# link_logic.net
KiCad netlist of a schematic drawn in Altium Designer
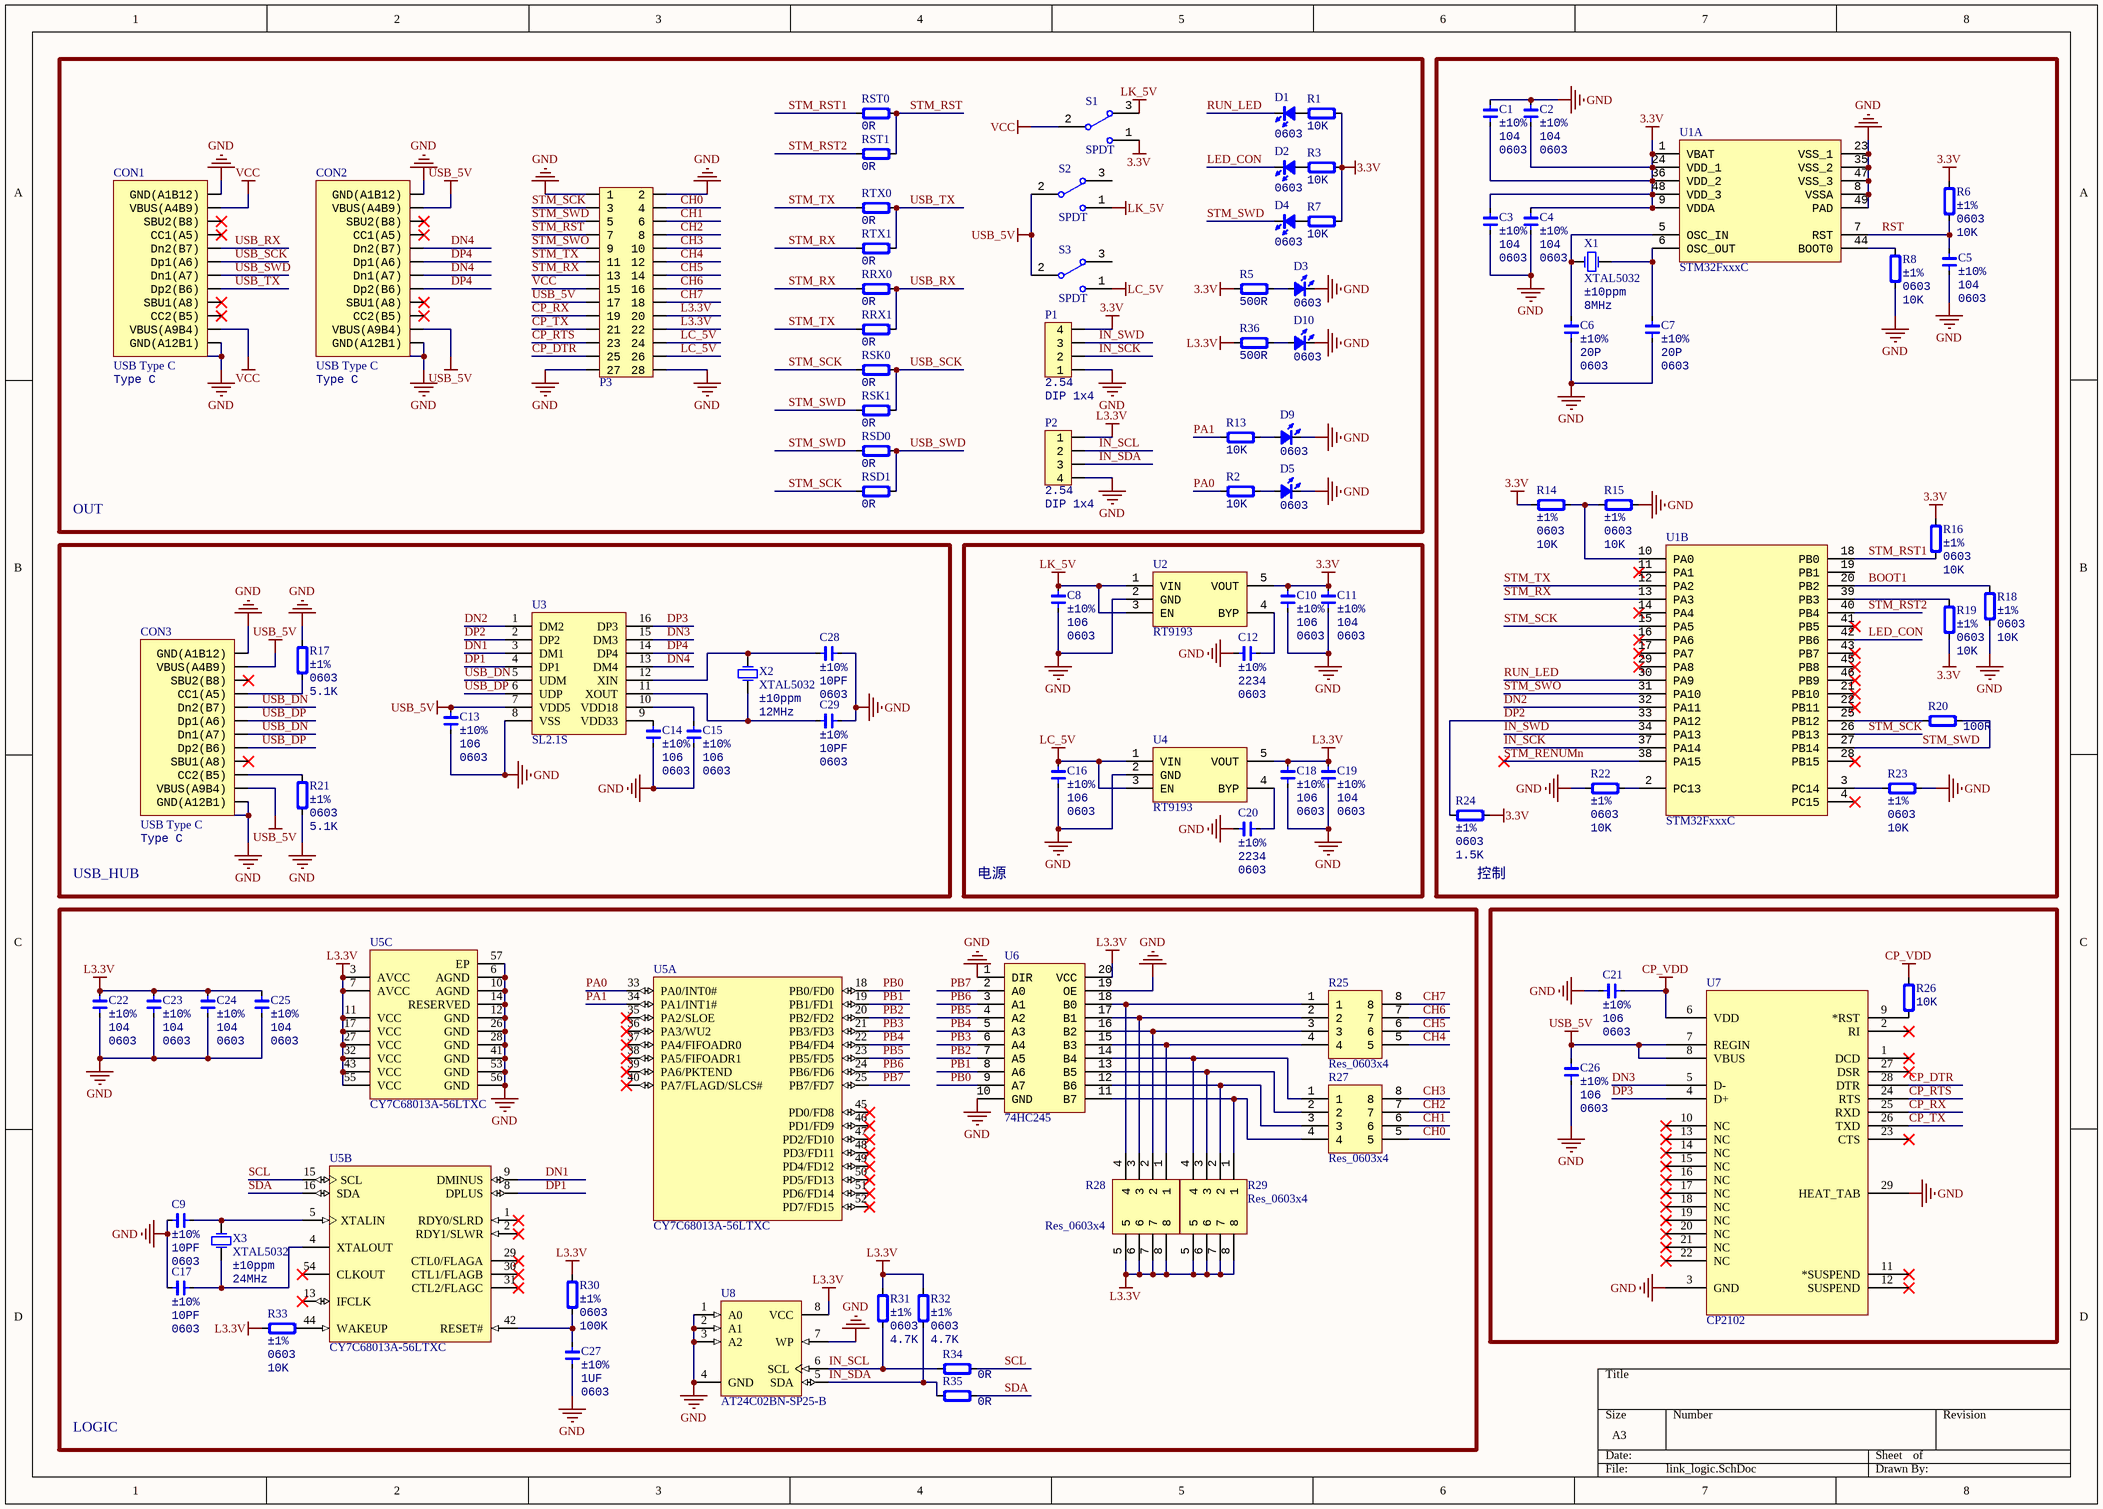
[diagram p0: link_logic.SchDoc]

(export (version "E")
  (design (tool "Eeschema 10.0.6"))
  (components
    (comp (ref "C1")
      (value "104")
      (footprint "CAP_0603")
      (description "Capacitor")
      (fields (field (name "NOTE") "±10%") (field (name "TYPE") "0603") (field (name "Comment") "C0603"))
      (libsource (lib "Integrated_Library") (part "Cap_0603"))
    )
    (comp (ref "C2")
      (value "104")
      (footprint "CAP_0603")
      (description "Capacitor")
      (fields (field (name "NOTE") "±10%") (field (name "TYPE") "0603") (field (name "Comment") "C0603"))
      (libsource (lib "Integrated_Library") (part "Cap_0603"))
    )
    (comp (ref "C3")
      (value "104")
      (footprint "CAP_0603")
      (description "Capacitor")
      (fields (field (name "NOTE") "±10%") (field (name "TYPE") "0603") (field (name "Comment") "C0603"))
      (libsource (lib "Integrated_Library") (part "Cap_0603"))
    )
    (comp (ref "C4")
      (value "104")
      (footprint "CAP_0603")
      (description "Capacitor")
      (fields (field (name "NOTE") "±10%") (field (name "TYPE") "0603") (field (name "Comment") "C0603"))
      (libsource (lib "Integrated_Library") (part "Cap_0603"))
    )
    (comp (ref "C5")
      (value "104")
      (footprint "CAP_0603")
      (description "Capacitor")
      (fields (field (name "NOTE") "±10%") (field (name "TYPE") "0603") (field (name "Comment") "C0603"))
      (libsource (lib "Integrated_Library") (part "Cap_0603"))
    )
    (comp (ref "C6")
      (value "20P")
      (footprint "CAP_0603")
      (description "Capacitor")
      (fields (field (name "NOTE") "±10%") (field (name "TYPE") "0603") (field (name "Comment") "C0603"))
      (libsource (lib "Integrated_Library") (part "Cap_0603"))
    )
    (comp (ref "C7")
      (value "20P")
      (footprint "CAP_0603")
      (description "Capacitor")
      (fields (field (name "NOTE") "±10%") (field (name "TYPE") "0603") (field (name "Comment") "C0603"))
      (libsource (lib "Integrated_Library") (part "Cap_0603"))
    )
    (comp (ref "C8")
      (value "106")
      (footprint "CAP_0603")
      (description "Capacitor")
      (fields (field (name "NOTE") "±10%") (field (name "TYPE") "0603") (field (name "Comment") "C0603"))
      (libsource (lib "Integrated_Library") (part "Cap_0603"))
    )
    (comp (ref "C9")
      (value "10PF")
      (footprint "CAP_0603")
      (description "Capacitor")
      (fields (field (name "NOTE") "±10%") (field (name "TYPE") "0603") (field (name "Comment") "C0603"))
      (libsource (lib "") (part "Cap_0603_3"))
    )
    (comp (ref "C10")
      (value "106")
      (footprint "CAP_0603")
      (description "Capacitor")
      (fields (field (name "NOTE") "±10%") (field (name "TYPE") "0603") (field (name "Comment") "C0603"))
      (libsource (lib "Integrated_Library") (part "Cap_0603"))
    )
    (comp (ref "C11")
      (value "104")
      (footprint "CAP_0603")
      (description "Capacitor")
      (fields (field (name "NOTE") "±10%") (field (name "TYPE") "0603") (field (name "Comment") "C0603"))
      (libsource (lib "Integrated_Library") (part "Cap_0603"))
    )
    (comp (ref "C12")
      (value "2234")
      (footprint "CAP_0603")
      (description "Capacitor")
      (fields (field (name "NOTE") "±10%") (field (name "TYPE") "0603") (field (name "Comment") "C0603"))
      (libsource (lib "") (part "Cap_0603_1"))
    )
    (comp (ref "C13")
      (value "106")
      (footprint "CAP_0603")
      (description "Capacitor")
      (fields (field (name "NOTE") "±10%") (field (name "TYPE") "0603") (field (name "Comment") "C0603"))
      (libsource (lib "Integrated_Library") (part "Cap_0603"))
    )
    (comp (ref "C14")
      (value "106")
      (footprint "CAP_0603")
      (description "Capacitor")
      (fields (field (name "NOTE") "±10%") (field (name "TYPE") "0603") (field (name "Comment") "C0603"))
      (libsource (lib "") (part "Cap_0603_2"))
    )
    (comp (ref "C15")
      (value "106")
      (footprint "CAP_0603")
      (description "Capacitor")
      (fields (field (name "NOTE") "±10%") (field (name "TYPE") "0603") (field (name "Comment") "C0603"))
      (libsource (lib "") (part "Cap_0603_2"))
    )
    (comp (ref "C16")
      (value "106")
      (footprint "CAP_0603")
      (description "Capacitor")
      (fields (field (name "NOTE") "±10%") (field (name "TYPE") "0603") (field (name "Comment") "C0603"))
      (libsource (lib "Integrated_Library") (part "Cap_0603"))
    )
    (comp (ref "C17")
      (value "10PF")
      (footprint "CAP_0603")
      (description "Capacitor")
      (fields (field (name "NOTE") "±10%") (field (name "TYPE") "0603") (field (name "Comment") "C0603"))
      (libsource (lib "") (part "Cap_0603_3"))
    )
    (comp (ref "C18")
      (value "106")
      (footprint "CAP_0603")
      (description "Capacitor")
      (fields (field (name "NOTE") "±10%") (field (name "TYPE") "0603") (field (name "Comment") "C0603"))
      (libsource (lib "Integrated_Library") (part "Cap_0603"))
    )
    (comp (ref "C19")
      (value "104")
      (footprint "CAP_0603")
      (description "Capacitor")
      (fields (field (name "NOTE") "±10%") (field (name "TYPE") "0603") (field (name "Comment") "C0603"))
      (libsource (lib "Integrated_Library") (part "Cap_0603"))
    )
    (comp (ref "C20")
      (value "2234")
      (footprint "CAP_0603")
      (description "Capacitor")
      (fields (field (name "NOTE") "±10%") (field (name "TYPE") "0603") (field (name "Comment") "C0603"))
      (libsource (lib "") (part "Cap_0603_1"))
    )
    (comp (ref "C21")
      (value "106")
      (footprint "CAP_0603")
      (description "Capacitor")
      (fields (field (name "NOTE") "±10%") (field (name "TYPE") "0603") (field (name "Comment") "C0603"))
      (libsource (lib "") (part "Cap_0603_1"))
    )
    (comp (ref "C22")
      (value "104")
      (footprint "CAP_0603")
      (description "Capacitor")
      (fields (field (name "NOTE") "±10%") (field (name "TYPE") "0603") (field (name "Comment") "C0603"))
      (libsource (lib "") (part "Cap_0603_2"))
    )
    (comp (ref "C23")
      (value "104")
      (footprint "CAP_0603")
      (description "Capacitor")
      (fields (field (name "NOTE") "±10%") (field (name "TYPE") "0603") (field (name "Comment") "C0603"))
      (libsource (lib "") (part "Cap_0603_2"))
    )
    (comp (ref "C24")
      (value "104")
      (footprint "CAP_0603")
      (description "Capacitor")
      (fields (field (name "NOTE") "±10%") (field (name "TYPE") "0603") (field (name "Comment") "C0603"))
      (libsource (lib "") (part "Cap_0603_2"))
    )
    (comp (ref "C25")
      (value "104")
      (footprint "CAP_0603")
      (description "Capacitor")
      (fields (field (name "NOTE") "±10%") (field (name "TYPE") "0603") (field (name "Comment") "C0603"))
      (libsource (lib "") (part "Cap_0603_2"))
    )
    (comp (ref "C26")
      (value "106")
      (footprint "CAP_0603")
      (description "Capacitor")
      (fields (field (name "NOTE") "±10%") (field (name "TYPE") "0603") (field (name "Comment") "C0603"))
      (libsource (lib "Integrated_Library") (part "Cap_0603"))
    )
    (comp (ref "C27")
      (value "1UF")
      (footprint "CAP_0603")
      (description "Capacitor")
      (fields (field (name "NOTE") "±10%") (field (name "TYPE") "0603") (field (name "Comment") "C0603"))
      (libsource (lib "Integrated_Library") (part "Cap_0603"))
    )
    (comp (ref "C28")
      (value "10PF")
      (footprint "CAP_0603")
      (description "Capacitor")
      (fields (field (name "NOTE") "±10%") (field (name "TYPE") "0603") (field (name "Comment") "C0603"))
      (libsource (lib "") (part "Cap_0603_1"))
    )
    (comp (ref "C29")
      (value "10PF")
      (footprint "CAP_0603")
      (description "Capacitor")
      (fields (field (name "NOTE") "±10%") (field (name "TYPE") "0603") (field (name "Comment") "C0603"))
      (libsource (lib "") (part "Cap_0603_1"))
    )
    (comp (ref "CON1")
      (value "USB Type C")
      (footprint "TYPEC_16P_TOP")
      (description "USB")
      (fields (field (name "ALTIUM_VALUE") "Type C"))
      (libsource (lib "Integrated_Library") (part "USB_TypeC_16P"))
    )
    (comp (ref "CON2")
      (value "USB Type C")
      (footprint "TYPEC_16P_TOP")
      (description "USB")
      (fields (field (name "ALTIUM_VALUE") "Type C"))
      (libsource (lib "Integrated_Library") (part "USB_TypeC_16P"))
    )
    (comp (ref "CON3")
      (value "USB Type C")
      (footprint "TYPEC_16P_TOP")
      (description "USB")
      (fields (field (name "ALTIUM_VALUE") "Type C"))
      (libsource (lib "Integrated_Library") (part "USB_TypeC_16P"))
    )
    (comp (ref "D1")
      (value "D0603")
      (footprint "LED_0603_RED")
      (description "LED")
      (fields (field (name "TYPE") "0603"))
      (libsource (lib "Integrated_Library") (part "LED_0603"))
    )
    (comp (ref "D2")
      (value "D0603")
      (footprint "LED_0603_RED")
      (description "LED")
      (fields (field (name "TYPE") "0603"))
      (libsource (lib "Integrated_Library") (part "LED_0603"))
    )
    (comp (ref "D3")
      (value "D0603")
      (footprint "LED_0603_RED")
      (description "LED")
      (fields (field (name "TYPE") "0603"))
      (libsource (lib "") (part "LED_0603_1"))
    )
    (comp (ref "D4")
      (value "D0603")
      (footprint "LED_0603_RED")
      (description "LED")
      (fields (field (name "TYPE") "0603"))
      (libsource (lib "Integrated_Library") (part "LED_0603"))
    )
    (comp (ref "D5")
      (value "D0603")
      (footprint "LED_0603_RED")
      (description "LED")
      (fields (field (name "TYPE") "0603"))
      (libsource (lib "") (part "LED_0603_1"))
    )
    (comp (ref "D9")
      (value "D0603")
      (footprint "LED_0603_RED")
      (description "LED")
      (fields (field (name "TYPE") "0603"))
      (libsource (lib "") (part "LED_0603_1"))
    )
    (comp (ref "D10")
      (value "D0603")
      (footprint "LED_0603_RED")
      (description "LED")
      (fields (field (name "TYPE") "0603"))
      (libsource (lib "") (part "LED_0603_1"))
    )
    (comp (ref "P1")
      (value "2.54")
      (footprint "HDR1X4_2.54_T")
      (description "Header Top")
      (fields (field (name "TYPE") "DIP 1x4") (field (name "Comment") "HDR1x4"))
      (libsource (lib "") (part "HDR1x4_2.54TOP_1"))
    )
    (comp (ref "P2")
      (value "2.54")
      (footprint "HDR1X4_2.54_T")
      (description "Header Top")
      (fields (field (name "TYPE") "DIP 1x4") (field (name "Comment") "HDR1x4"))
      (libsource (lib "Integrated_Library") (part "HDR1x4_2.54TOP"))
    )
    (comp (ref "P3")
      (value "HDR2x14_2.54TOP")
      (footprint "HDR2X14_2.54_T")
      (description "Header Top")
      (libsource (lib "Integrated_Library") (part "HDR2x14_2.54TOP"))
    )
    (comp (ref "R1")
      (value "10K")
      (footprint "RES_0603")
      (description "Resistor")
      (fields (field (name "Comment") "R0603"))
      (libsource (lib "Integrated_Library") (part "Res_0603"))
    )
    (comp (ref "R2")
      (value "10K")
      (footprint "RES_0603")
      (description "Resistor")
      (fields (field (name "Comment") "R0603"))
      (libsource (lib "Integrated_Library") (part "Res_0603"))
    )
    (comp (ref "R3")
      (value "10K")
      (footprint "RES_0603")
      (description "Resistor")
      (fields (field (name "Comment") "R0603"))
      (libsource (lib "Integrated_Library") (part "Res_0603"))
    )
    (comp (ref "R5")
      (value "500R")
      (footprint "RES_0603")
      (description "Resistor")
      (fields (field (name "Comment") "R0603"))
      (libsource (lib "Integrated_Library") (part "Res_0603"))
    )
    (comp (ref "R6")
      (value "10K")
      (footprint "RES_0603")
      (description "Resistor")
      (fields (field (name "NOTE") "±1%") (field (name "TYPE") "0603") (field (name "Comment") "R0603"))
      (libsource (lib "Integrated_Library") (part "Res_0603"))
    )
    (comp (ref "R7")
      (value "10K")
      (footprint "RES_0603")
      (description "Resistor")
      (fields (field (name "Comment") "R0603"))
      (libsource (lib "Integrated_Library") (part "Res_0603"))
    )
    (comp (ref "R8")
      (value "10K")
      (footprint "RES_0603")
      (description "Resistor")
      (fields (field (name "NOTE") "±1%") (field (name "TYPE") "0603") (field (name "Comment") "R0603"))
      (libsource (lib "Integrated_Library") (part "Res_0603"))
    )
    (comp (ref "R13")
      (value "10K")
      (footprint "RES_0603")
      (description "Resistor")
      (fields (field (name "Comment") "R0603"))
      (libsource (lib "Integrated_Library") (part "Res_0603"))
    )
    (comp (ref "R14")
      (value "10K")
      (footprint "RES_0603")
      (description "Resistor")
      (fields (field (name "NOTE") "±1%") (field (name "TYPE") "0603") (field (name "Comment") "R0603"))
      (libsource (lib "Integrated_Library") (part "Res_0603"))
    )
    (comp (ref "R15")
      (value "10K")
      (footprint "RES_0603")
      (description "Resistor")
      (fields (field (name "NOTE") "±1%") (field (name "TYPE") "0603") (field (name "Comment") "R0603"))
      (libsource (lib "Integrated_Library") (part "Res_0603"))
    )
    (comp (ref "R16")
      (value "10K")
      (footprint "RES_0603")
      (description "Resistor")
      (fields (field (name "NOTE") "±1%") (field (name "TYPE") "0603") (field (name "Comment") "R0603"))
      (libsource (lib "Integrated_Library") (part "Res_0603"))
    )
    (comp (ref "R17")
      (value "5.1K")
      (footprint "RES_0603")
      (description "Resistor")
      (fields (field (name "NOTE") "±1%") (field (name "TYPE") "0603") (field (name "Comment") "R0603"))
      (libsource (lib "Integrated_Library") (part "Res_0603"))
    )
    (comp (ref "R18")
      (value "10K")
      (footprint "RES_0603")
      (description "Resistor")
      (fields (field (name "NOTE") "±1%") (field (name "TYPE") "0603") (field (name "Comment") "R0603"))
      (libsource (lib "Integrated_Library") (part "Res_0603"))
    )
    (comp (ref "R19")
      (value "10K")
      (footprint "RES_0603")
      (description "Resistor")
      (fields (field (name "NOTE") "±1%") (field (name "TYPE") "0603") (field (name "Comment") "R0603"))
      (libsource (lib "Integrated_Library") (part "Res_0603"))
    )
    (comp (ref "R20")
      (value "100R")
      (footprint "RES_0603")
      (description "Resistor")
      (fields (field (name "Comment") "R0603"))
      (libsource (lib "Integrated_Library") (part "Res_0603"))
    )
    (comp (ref "R21")
      (value "5.1K")
      (footprint "RES_0603")
      (description "Resistor")
      (fields (field (name "NOTE") "±1%") (field (name "TYPE") "0603") (field (name "Comment") "R0603"))
      (libsource (lib "Integrated_Library") (part "Res_0603"))
    )
    (comp (ref "R22")
      (value "10K")
      (footprint "RES_0603")
      (description "Resistor")
      (fields (field (name "NOTE") "±1%") (field (name "TYPE") "0603") (field (name "Comment") "R0603"))
      (libsource (lib "Integrated_Library") (part "Res_0603"))
    )
    (comp (ref "R23")
      (value "10K")
      (footprint "RES_0603")
      (description "Resistor")
      (fields (field (name "NOTE") "±1%") (field (name "TYPE") "0603") (field (name "Comment") "R0603"))
      (libsource (lib "Integrated_Library") (part "Res_0603"))
    )
    (comp (ref "R24")
      (value "1.5K")
      (footprint "RES_0603")
      (description "Resistor")
      (fields (field (name "NOTE") "±1%") (field (name "TYPE") "0603") (field (name "Comment") "R0603"))
      (libsource (lib "Integrated_Library") (part "Res_0603"))
    )
    (comp (ref "R25")
      (value "Res_0603x4")
      (footprint "RES_0603X4")
      (description "Resistor")
      (libsource (lib "") (part "Res_0603x4_1"))
    )
    (comp (ref "R26")
      (value "10K")
      (footprint "RES_0603")
      (description "Resistor")
      (fields (field (name "Comment") "R0603"))
      (libsource (lib "Integrated_Library") (part "Res_0603"))
    )
    (comp (ref "R27")
      (value "Res_0603x4")
      (footprint "RES_0603X4")
      (description "Resistor")
      (libsource (lib "") (part "Res_0603x4_1"))
    )
    (comp (ref "R28")
      (value "Res_0603x4")
      (footprint "RES_0603X4")
      (description "Resistor")
      (libsource (lib "Integrated_Library") (part "Res_0603x4"))
    )
    (comp (ref "R29")
      (value "Res_0603x4")
      (footprint "RES_0603X4")
      (description "Resistor")
      (libsource (lib "Integrated_Library") (part "Res_0603x4"))
    )
    (comp (ref "R30")
      (value "100K")
      (footprint "RES_0603")
      (description "Resistor")
      (fields (field (name "NOTE") "±1%") (field (name "TYPE") "0603") (field (name "Comment") "R0603"))
      (libsource (lib "Integrated_Library") (part "Res_0603"))
    )
    (comp (ref "R31")
      (value "4.7K")
      (footprint "RES_0603")
      (description "Resistor")
      (fields (field (name "NOTE") "±1%") (field (name "TYPE") "0603") (field (name "Comment") "R0603"))
      (libsource (lib "Integrated_Library") (part "Res_0603"))
    )
    (comp (ref "R32")
      (value "4.7K")
      (footprint "RES_0603")
      (description "Resistor")
      (fields (field (name "NOTE") "±1%") (field (name "TYPE") "0603") (field (name "Comment") "R0603"))
      (libsource (lib "Integrated_Library") (part "Res_0603"))
    )
    (comp (ref "R33")
      (value "10K")
      (footprint "RES_0603")
      (description "Resistor")
      (fields (field (name "NOTE") "±1%") (field (name "TYPE") "0603") (field (name "Comment") "R0603"))
      (libsource (lib "Integrated_Library") (part "Res_0603"))
    )
    (comp (ref "R34")
      (value "0R")
      (footprint "RES_0603")
      (description "Resistor")
      (fields (field (name "Comment") "R0603"))
      (libsource (lib "Integrated_Library") (part "Res_0603"))
    )
    (comp (ref "R35")
      (value "0R")
      (footprint "RES_0603")
      (description "Resistor")
      (fields (field (name "Comment") "R0603"))
      (libsource (lib "Integrated_Library") (part "Res_0603"))
    )
    (comp (ref "R36")
      (value "500R")
      (footprint "RES_0603")
      (description "Resistor")
      (fields (field (name "Comment") "R0603"))
      (libsource (lib "Integrated_Library") (part "Res_0603"))
    )
    (comp (ref "RRX0")
      (value "0R")
      (footprint "RES_0603")
      (description "Resistor")
      (fields (field (name "Comment") "R0603"))
      (libsource (lib "Integrated_Library") (part "Res_0603"))
    )
    (comp (ref "RRX1")
      (value "0R")
      (footprint "RES_0603")
      (description "Resistor")
      (fields (field (name "Comment") "R0603"))
      (libsource (lib "Integrated_Library") (part "Res_0603"))
    )
    (comp (ref "RSD0")
      (value "0R")
      (footprint "RES_0603")
      (description "Resistor")
      (fields (field (name "Comment") "R0603"))
      (libsource (lib "Integrated_Library") (part "Res_0603"))
    )
    (comp (ref "RSD1")
      (value "0R")
      (footprint "RES_0603")
      (description "Resistor")
      (fields (field (name "Comment") "R0603"))
      (libsource (lib "Integrated_Library") (part "Res_0603"))
    )
    (comp (ref "RSK0")
      (value "0R")
      (footprint "RES_0603")
      (description "Resistor")
      (fields (field (name "Comment") "R0603"))
      (libsource (lib "Integrated_Library") (part "Res_0603"))
    )
    (comp (ref "RSK1")
      (value "0R")
      (footprint "RES_0603")
      (description "Resistor")
      (fields (field (name "Comment") "R0603"))
      (libsource (lib "Integrated_Library") (part "Res_0603"))
    )
    (comp (ref "RST0")
      (value "0R")
      (footprint "RES_0603")
      (description "Resistor")
      (fields (field (name "Comment") "R0603"))
      (libsource (lib "Integrated_Library") (part "Res_0603"))
    )
    (comp (ref "RST1")
      (value "0R")
      (footprint "RES_0603")
      (description "Resistor")
      (fields (field (name "Comment") "R0603"))
      (libsource (lib "Integrated_Library") (part "Res_0603"))
    )
    (comp (ref "RTX0")
      (value "0R")
      (footprint "RES_0603")
      (description "Resistor")
      (fields (field (name "Comment") "R0603"))
      (libsource (lib "Integrated_Library") (part "Res_0603"))
    )
    (comp (ref "RTX1")
      (value "0R")
      (footprint "RES_0603")
      (description "Resistor")
      (fields (field (name "Comment") "R0603"))
      (libsource (lib "Integrated_Library") (part "Res_0603"))
    )
    (comp (ref "S1")
      (value "SPDT")
      (footprint "SwitchSPDT_2.8X6.6_90")
      (description "Switch")
      (libsource (lib "Integrated_Library") (part "SwitchSPDT_90_2.8x6.6"))
    )
    (comp (ref "S2")
      (value "SPDT")
      (footprint "SwitchSPDT_2.8X6.6_90")
      (description "Switch")
      (libsource (lib "Integrated_Library") (part "SwitchSPDT_90_2.8x6.6"))
    )
    (comp (ref "S3")
      (value "SPDT")
      (footprint "SwitchSPDT_2.8X6.6_90")
      (description "Switch")
      (libsource (lib "Integrated_Library") (part "SwitchSPDT_90_2.8x6.6"))
    )
    (comp (ref "U1")
      (value "STM32FxxxC")
      (footprint "LQFP_QNF_48")
      (description "MCU ST")
      (fields (field (name "MANUFACTURER") "STMicroelectronics"))
      (libsource (lib "Integrated_Library") (part "STM32FxxxC"))
    )
    (comp (ref "U2")
      (value "RT9193")
      (footprint "SOT23-5")
      (description "Power")
      (libsource (lib "Integrated_Library") (part "RT9193"))
    )
    (comp (ref "U3")
      (value "SL2.1S")
      (footprint "PCBLIB:TSSOP16")
      (description "USB HUB")
      (libsource (lib "Integrated_Library") (part "SL2.1S"))
    )
    (comp (ref "U4")
      (value "RT9193")
      (footprint "SOT23-5")
      (description "Power")
      (libsource (lib "Integrated_Library") (part "RT9193"))
    )
    (comp (ref "U5")
      (value "CY7C68013A-56LTXC")
      (footprint "CYP-LTX56-5200X4500TP_N")
      (fields (field (name "MANUFACTURER") "Cypress"))
      (libsource (lib "Cypress USB Controllers") (part "CY7C68013A-56LTXC"))
    )
    (comp (ref "U6")
      (value "74HC245")
      (footprint "SOP_E300_20")
      (description "74 Series")
      (libsource (lib "Integrated_Library") (part "74HC245"))
    )
    (comp (ref "U7")
      (value "CP2102")
      (footprint "QFN-28")
      (libsource (lib "Integrated_Library") (part "CP2102"))
    )
    (comp (ref "U8")
      (value "AT24C02BN-SP25-B")
      (footprint "8S1_N")
      (libsource (lib "Atmel Serial EEPROM") (part "AT24C02BN-SP25-B"))
    )
    (comp (ref "X1")
      (value "XTAL5032")
      (footprint "XT_5032_2")
      (description "Crystal Oscillator")
      (fields (field (name "SPECIFICATION") "±10ppm") (field (name "ALTIUM_VALUE") "8MHz"))
      (libsource (lib "Integrated_Library") (part "XTAL_5032_2P"))
    )
    (comp (ref "X2")
      (value "XTAL5032")
      (footprint "XT_5032_2")
      (description "Crystal Oscillator")
      (fields (field (name "SPECIFICATION") "±10ppm") (field (name "ALTIUM_VALUE") "12MHz"))
      (libsource (lib "Integrated_Library") (part "XTAL_5032_2P"))
    )
    (comp (ref "X3")
      (value "XTAL5032")
      (footprint "XT_5032_2")
      (description "Crystal Oscillator")
      (fields (field (name "SPECIFICATION") "±10ppm") (field (name "ALTIUM_VALUE") "24MHz"))
      (libsource (lib "Integrated_Library") (part "XTAL_5032_2P"))
    )
  )
  (nets
    (net (code "1") (name "/BOOT1") (class "Default")
      (node (ref "R18") (pin "1") (pinfunction "1_1") (pintype "passive"))
      (node (ref "U1") (pin "20") (pinfunction "PB2_20") (pintype "passive"))
    )
    (net (code "2") (name "/CH0") (class "Default")
      (node (ref "P3") (pin "4") (pinfunction "4_4") (pintype "passive"))
      (node (ref "R27") (pin "5") (pinfunction "5_5") (pintype "passive"))
    )
    (net (code "3") (name "/CH1") (class "Default")
      (node (ref "P3") (pin "6") (pinfunction "6_6") (pintype "passive"))
      (node (ref "R27") (pin "6") (pinfunction "6_6") (pintype "passive"))
    )
    (net (code "4") (name "/CH2") (class "Default")
      (node (ref "P3") (pin "8") (pinfunction "8_8") (pintype "passive"))
      (node (ref "R27") (pin "7") (pinfunction "7_7") (pintype "passive"))
    )
    (net (code "5") (name "/CH3") (class "Default")
      (node (ref "P3") (pin "10") (pinfunction "10_10") (pintype "passive"))
      (node (ref "R27") (pin "8") (pinfunction "8_8") (pintype "passive"))
    )
    (net (code "6") (name "/CH4") (class "Default")
      (node (ref "P3") (pin "12") (pinfunction "12_12") (pintype "passive"))
      (node (ref "R25") (pin "5") (pinfunction "5_5") (pintype "passive"))
    )
    (net (code "7") (name "/CH5") (class "Default")
      (node (ref "P3") (pin "14") (pinfunction "14_14") (pintype "passive"))
      (node (ref "R25") (pin "6") (pinfunction "6_6") (pintype "passive"))
    )
    (net (code "8") (name "/CH6") (class "Default")
      (node (ref "P3") (pin "16") (pinfunction "16_16") (pintype "passive"))
      (node (ref "R25") (pin "7") (pinfunction "7_7") (pintype "passive"))
    )
    (net (code "9") (name "/CH7") (class "Default")
      (node (ref "P3") (pin "18") (pinfunction "18_18") (pintype "passive"))
      (node (ref "R25") (pin "8") (pinfunction "8_8") (pintype "passive"))
    )
    (net (code "10") (name "/CP_DTR") (class "Default")
      (node (ref "P3") (pin "25") (pinfunction "25_25") (pintype "passive"))
      (node (ref "U7") (pin "28") (pinfunction "DTR_28") (pintype "passive"))
    )
    (net (code "11") (name "/CP_RTS") (class "Default")
      (node (ref "P3") (pin "23") (pinfunction "23_23") (pintype "passive"))
      (node (ref "U7") (pin "24") (pinfunction "RTS_24") (pintype "passive"))
    )
    (net (code "12") (name "/CP_RX") (class "Default")
      (node (ref "P3") (pin "19") (pinfunction "19_19") (pintype "passive"))
      (node (ref "U7") (pin "25") (pinfunction "RXD_25") (pintype "passive"))
    )
    (net (code "13") (name "/CP_TX") (class "Default")
      (node (ref "P3") (pin "21") (pinfunction "21_21") (pintype "passive"))
      (node (ref "U7") (pin "26") (pinfunction "TXD_26") (pintype "passive"))
    )
    (net (code "14") (name "/DN1") (class "Default")
      (node (ref "U3") (pin "3") (pinfunction "DM1_3") (pintype "passive"))
      (node (ref "U5") (pin "9") (pinfunction "DMINUS_9") (pintype "bidirectional"))
    )
    (net (code "15") (name "/DN2") (class "Default")
      (node (ref "U1") (pin "32") (pinfunction "PA11_32") (pintype "passive"))
      (node (ref "U3") (pin "1") (pinfunction "DM2_1") (pintype "passive"))
    )
    (net (code "16") (name "/DN3") (class "Default")
      (node (ref "U3") (pin "15") (pinfunction "DM3_15") (pintype "passive"))
      (node (ref "U7") (pin "5") (pinfunction "D-_5") (pintype "passive"))
    )
    (net (code "17") (name "/DN4") (class "Default")
      (node (ref "CON2") (pin "A7") (pinfunction "Dn1(A7)_A7") (pintype "passive"))
      (node (ref "CON2") (pin "B7") (pinfunction "Dn2(B7)_B7") (pintype "passive"))
      (node (ref "U3") (pin "13") (pinfunction "DM4_13") (pintype "passive"))
    )
    (net (code "18") (name "/DP1") (class "Default")
      (node (ref "U3") (pin "4") (pinfunction "DP1_4") (pintype "passive"))
      (node (ref "U5") (pin "8") (pinfunction "DPLUS_8") (pintype "bidirectional"))
    )
    (net (code "19") (name "/DP2") (class "Default")
      (node (ref "R24") (pin "1") (pinfunction "1_1") (pintype "passive"))
      (node (ref "U1") (pin "33") (pinfunction "PA12_33") (pintype "passive"))
      (node (ref "U3") (pin "2") (pinfunction "DP2_2") (pintype "passive"))
    )
    (net (code "20") (name "/DP3") (class "Default")
      (node (ref "U3") (pin "16") (pinfunction "DP3_16") (pintype "passive"))
      (node (ref "U7") (pin "4") (pinfunction "D+_4") (pintype "passive"))
    )
    (net (code "21") (name "/DP4") (class "Default")
      (node (ref "CON2") (pin "A6") (pinfunction "Dp1(A6)_A6") (pintype "passive"))
      (node (ref "CON2") (pin "B6") (pinfunction "Dp2(B6)_B6") (pintype "passive"))
      (node (ref "U3") (pin "14") (pinfunction "DP4_14") (pintype "passive"))
    )
    (net (code "22") (name "/IN_SCK") (class "Default")
      (node (ref "P1") (pin "2") (pinfunction "2_2") (pintype "passive"))
      (node (ref "U1") (pin "37") (pinfunction "PA14_37") (pintype "passive"))
    )
    (net (code "23") (name "/IN_SCL") (class "Default")
      (node (ref "P2") (pin "2") (pinfunction "2_2") (pintype "passive"))
      (node (ref "R31") (pin "1") (pinfunction "1_1") (pintype "passive"))
      (node (ref "R34") (pin "2") (pinfunction "2_2") (pintype "passive"))
      (node (ref "U8") (pin "6") (pinfunction "SCL_6") (pintype "input"))
    )
    (net (code "24") (name "/IN_SDA") (class "Default")
      (node (ref "P2") (pin "3") (pinfunction "3_3") (pintype "passive"))
      (node (ref "R32") (pin "2") (pinfunction "2_2") (pintype "passive"))
      (node (ref "R35") (pin "2") (pinfunction "2_2") (pintype "passive"))
      (node (ref "U8") (pin "5") (pinfunction "SDA_5") (pintype "bidirectional"))
    )
    (net (code "25") (name "/IN_SWD") (class "Default")
      (node (ref "P1") (pin "3") (pinfunction "3_3") (pintype "passive"))
      (node (ref "U1") (pin "34") (pinfunction "PA13_34") (pintype "passive"))
    )
    (net (code "26") (name "/LED_CON") (class "Default")
      (node (ref "D2") (pin "2") (pinfunction "K_2") (pintype "passive"))
      (node (ref "U1") (pin "42") (pinfunction "PB6_42") (pintype "passive"))
    )
    (net (code "27") (name "/PA0") (class "Default")
      (node (ref "R2") (pin "2") (pinfunction "2_2") (pintype "passive"))
      (node (ref "U5") (pin "33") (pinfunction "PA0/INT0#_33") (pintype "bidirectional"))
    )
    (net (code "28") (name "/PA1") (class "Default")
      (node (ref "R13") (pin "2") (pinfunction "2_2") (pintype "passive"))
      (node (ref "U5") (pin "34") (pinfunction "PA1/INT1#_34") (pintype "bidirectional"))
    )
    (net (code "29") (name "/PB0") (class "Default")
      (node (ref "U5") (pin "18") (pinfunction "PB0/FD0_18") (pintype "bidirectional"))
      (node (ref "U6") (pin "9") (pinfunction "A7_9") (pintype "passive"))
    )
    (net (code "30") (name "/PB1") (class "Default")
      (node (ref "U5") (pin "19") (pinfunction "PB1/FD1_19") (pintype "bidirectional"))
      (node (ref "U6") (pin "8") (pinfunction "A6_8") (pintype "passive"))
    )
    (net (code "31") (name "/PB2") (class "Default")
      (node (ref "U5") (pin "20") (pinfunction "PB2/FD2_20") (pintype "bidirectional"))
      (node (ref "U6") (pin "7") (pinfunction "A5_7") (pintype "passive"))
    )
    (net (code "32") (name "/PB3") (class "Default")
      (node (ref "U5") (pin "21") (pinfunction "PB3/FD3_21") (pintype "bidirectional"))
      (node (ref "U6") (pin "6") (pinfunction "A4_6") (pintype "passive"))
    )
    (net (code "33") (name "/PB4") (class "Default")
      (node (ref "U5") (pin "22") (pinfunction "PB4/FD4_22") (pintype "bidirectional"))
      (node (ref "U6") (pin "5") (pinfunction "A3_5") (pintype "passive"))
    )
    (net (code "34") (name "/PB5") (class "Default")
      (node (ref "U5") (pin "23") (pinfunction "PB5/FD5_23") (pintype "bidirectional"))
      (node (ref "U6") (pin "4") (pinfunction "A2_4") (pintype "passive"))
    )
    (net (code "35") (name "/PB6") (class "Default")
      (node (ref "U5") (pin "24") (pinfunction "PB6/FD6_24") (pintype "bidirectional"))
      (node (ref "U6") (pin "3") (pinfunction "A1_3") (pintype "passive"))
    )
    (net (code "36") (name "/PB7") (class "Default")
      (node (ref "U5") (pin "25") (pinfunction "PB7/FD7_25") (pintype "bidirectional"))
      (node (ref "U6") (pin "2") (pinfunction "A0_2") (pintype "passive"))
    )
    (net (code "37") (name "/RST") (class "Default")
      (node (ref "C5") (pin "2") (pinfunction "2_2") (pintype "passive"))
      (node (ref "R6") (pin "1") (pinfunction "1_1") (pintype "passive"))
      (node (ref "U1") (pin "7") (pinfunction "RST_7") (pintype "passive"))
    )
    (net (code "38") (name "/RUN_LED") (class "Default")
      (node (ref "D1") (pin "2") (pinfunction "K_2") (pintype "passive"))
      (node (ref "U1") (pin "30") (pinfunction "PA9_30") (pintype "passive"))
    )
    (net (code "39") (name "/SCL") (class "Default")
      (node (ref "R34") (pin "1") (pinfunction "1_1") (pintype "passive"))
      (node (ref "U5") (pin "15") (pinfunction "SCL_15") (pintype "bidirectional"))
    )
    (net (code "40") (name "/SDA") (class "Default")
      (node (ref "R35") (pin "1") (pinfunction "1_1") (pintype "passive"))
      (node (ref "U5") (pin "16") (pinfunction "SDA_16") (pintype "bidirectional"))
    )
    (net (code "41") (name "/STM_RENUMn") (class "Default")
      (node (ref "U1") (pin "38") (pinfunction "PA15_38") (pintype "passive+no_connect"))
    )
    (net (code "42") (name "/STM_RST") (class "Default")
      (node (ref "P3") (pin "7") (pinfunction "7_7") (pintype "passive"))
      (node (ref "RST0") (pin "1") (pinfunction "1_1") (pintype "passive"))
      (node (ref "RST1") (pin "1") (pinfunction "1_1") (pintype "passive"))
    )
    (net (code "43") (name "/STM_RST1") (class "Default")
      (node (ref "R16") (pin "1") (pinfunction "1_1") (pintype "passive"))
      (node (ref "RST0") (pin "2") (pinfunction "2_2") (pintype "passive"))
      (node (ref "U1") (pin "18") (pinfunction "PB0_18") (pintype "passive"))
    )
    (net (code "44") (name "/STM_RST2") (class "Default")
      (node (ref "RST1") (pin "2") (pinfunction "2_2") (pintype "passive"))
      (node (ref "U1") (pin "40") (pinfunction "PB4_40") (pintype "passive"))
    )
    (net (code "45") (name "/STM_RX") (class "Default")
      (node (ref "P3") (pin "13") (pinfunction "13_13") (pintype "passive"))
      (node (ref "RRX0") (pin "2") (pinfunction "2_2") (pintype "passive"))
      (node (ref "RTX1") (pin "2") (pinfunction "2_2") (pintype "passive"))
      (node (ref "U1") (pin "13") (pinfunction "PA3_13") (pintype "passive"))
    )
    (net (code "46") (name "/STM_SCK") (class "Default")
      (node (ref "P3") (pin "3") (pinfunction "3_3") (pintype "passive"))
      (node (ref "RSD1") (pin "2") (pinfunction "2_2") (pintype "passive"))
      (node (ref "RSK0") (pin "2") (pinfunction "2_2") (pintype "passive"))
      (node (ref "U1") (pin "15") (pinfunction "PA5_15") (pintype "passive"))
      (node (ref "U1") (pin "26") (pinfunction "PB13_26") (pintype "passive"))
    )
    (net (code "47") (name "/STM_SWD") (class "Default")
      (node (ref "D4") (pin "2") (pinfunction "K_2") (pintype "passive"))
      (node (ref "P3") (pin "5") (pinfunction "5_5") (pintype "passive"))
      (node (ref "R20") (pin "1") (pinfunction "1_1") (pintype "passive"))
      (node (ref "RSD0") (pin "2") (pinfunction "2_2") (pintype "passive"))
      (node (ref "RSK1") (pin "2") (pinfunction "2_2") (pintype "passive"))
      (node (ref "U1") (pin "27") (pinfunction "PB14_27") (pintype "passive"))
    )
    (net (code "48") (name "/STM_SWO") (class "Default")
      (node (ref "P3") (pin "9") (pinfunction "9_9") (pintype "passive"))
      (node (ref "U1") (pin "31") (pinfunction "PA10_31") (pintype "passive"))
    )
    (net (code "49") (name "/STM_TX") (class "Default")
      (node (ref "P3") (pin "11") (pinfunction "11_11") (pintype "passive"))
      (node (ref "RRX1") (pin "2") (pinfunction "2_2") (pintype "passive"))
      (node (ref "RTX0") (pin "2") (pinfunction "2_2") (pintype "passive"))
      (node (ref "U1") (pin "12") (pinfunction "PA2_12") (pintype "passive"))
    )
    (net (code "50") (name "/USB_DN") (class "Default")
      (node (ref "CON3") (pin "A7") (pinfunction "Dn1(A7)_A7") (pintype "passive"))
      (node (ref "CON3") (pin "B7") (pinfunction "Dn2(B7)_B7") (pintype "passive"))
      (node (ref "U3") (pin "5") (pinfunction "UDM_5") (pintype "passive"))
    )
    (net (code "51") (name "/USB_DP") (class "Default")
      (node (ref "CON3") (pin "A6") (pinfunction "Dp1(A6)_A6") (pintype "passive"))
      (node (ref "CON3") (pin "B6") (pinfunction "Dp2(B6)_B6") (pintype "passive"))
      (node (ref "U3") (pin "6") (pinfunction "UDP_6") (pintype "passive"))
    )
    (net (code "52") (name "/USB_RX") (class "Default")
      (node (ref "CON1") (pin "B7") (pinfunction "Dn2(B7)_B7") (pintype "passive"))
      (node (ref "RRX0") (pin "1") (pinfunction "1_1") (pintype "passive"))
      (node (ref "RRX1") (pin "1") (pinfunction "1_1") (pintype "passive"))
    )
    (net (code "53") (name "/USB_SCK") (class "Default")
      (node (ref "CON1") (pin "A6") (pinfunction "Dp1(A6)_A6") (pintype "passive"))
      (node (ref "RSK0") (pin "1") (pinfunction "1_1") (pintype "passive"))
      (node (ref "RSK1") (pin "1") (pinfunction "1_1") (pintype "passive"))
    )
    (net (code "54") (name "/USB_SWD") (class "Default")
      (node (ref "CON1") (pin "A7") (pinfunction "Dn1(A7)_A7") (pintype "passive"))
      (node (ref "RSD0") (pin "1") (pinfunction "1_1") (pintype "passive"))
      (node (ref "RSD1") (pin "1") (pinfunction "1_1") (pintype "passive"))
    )
    (net (code "55") (name "/USB_TX") (class "Default")
      (node (ref "CON1") (pin "B6") (pinfunction "Dp2(B6)_B6") (pintype "passive"))
      (node (ref "RTX0") (pin "1") (pinfunction "1_1") (pintype "passive"))
      (node (ref "RTX1") (pin "1") (pinfunction "1_1") (pintype "passive"))
    )
    (net (code "56") (name "3.3V") (class "Default")
      (node (ref "C1") (pin "1") (pinfunction "1_1") (pintype "passive"))
      (node (ref "C10") (pin "2") (pinfunction "2_2") (pintype "passive"))
      (node (ref "C11") (pin "2") (pinfunction "2_2") (pintype "passive"))
      (node (ref "C2") (pin "1") (pinfunction "1_1") (pintype "passive"))
      (node (ref "C3") (pin "2") (pinfunction "2_2") (pintype "passive"))
      (node (ref "C4") (pin "2") (pinfunction "2_2") (pintype "passive"))
      (node (ref "P1") (pin "4") (pinfunction "4_4") (pintype "passive"))
      (node (ref "R1") (pin "1") (pinfunction "1_1") (pintype "passive"))
      (node (ref "R14") (pin "2") (pinfunction "2_2") (pintype "passive"))
      (node (ref "R16") (pin "2") (pinfunction "2_2") (pintype "passive"))
      (node (ref "R19") (pin "2") (pinfunction "2_2") (pintype "passive"))
      (node (ref "R24") (pin "2") (pinfunction "2_2") (pintype "passive"))
      (node (ref "R3") (pin "1") (pinfunction "1_1") (pintype "passive"))
      (node (ref "R5") (pin "1") (pinfunction "1_1") (pintype "passive"))
      (node (ref "R6") (pin "2") (pinfunction "2_2") (pintype "passive"))
      (node (ref "R7") (pin "1") (pinfunction "1_1") (pintype "passive"))
      (node (ref "S1") (pin "1") (pinfunction "1_1") (pintype "passive"))
      (node (ref "U1") (pin "1") (pinfunction "VBAT_1") (pintype "passive"))
      (node (ref "U1") (pin "24") (pinfunction "VDD_1_24") (pintype "passive"))
      (node (ref "U1") (pin "36") (pinfunction "VDD_2_36") (pintype "passive"))
      (node (ref "U1") (pin "48") (pinfunction "VDD_3_48") (pintype "passive"))
      (node (ref "U1") (pin "9") (pinfunction "VDDA_9") (pintype "passive"))
      (node (ref "U2") (pin "5") (pinfunction "VOUT_5") (pintype "passive"))
    )
    (net (code "57") (name "CP_VDD") (class "Default")
      (node (ref "C21") (pin "2") (pinfunction "2_2") (pintype "passive"))
      (node (ref "R26") (pin "2") (pinfunction "2_2") (pintype "passive"))
      (node (ref "U7") (pin "6") (pinfunction "VDD_6") (pintype "passive"))
    )
    (net (code "58") (name "GND") (class "Default")
      (node (ref "C1") (pin "2") (pinfunction "2_2") (pintype "passive"))
      (node (ref "C10") (pin "1") (pinfunction "1_1") (pintype "passive"))
      (node (ref "C11") (pin "1") (pinfunction "1_1") (pintype "passive"))
      (node (ref "C12") (pin "1") (pinfunction "1_1") (pintype "passive"))
      (node (ref "C13") (pin "1") (pinfunction "1_1") (pintype "passive"))
      (node (ref "C14") (pin "2") (pinfunction "2_2") (pintype "passive"))
      (node (ref "C15") (pin "2") (pinfunction "2_2") (pintype "passive"))
      (node (ref "C16") (pin "1") (pinfunction "1_1") (pintype "passive"))
      (node (ref "C17") (pin "2") (pinfunction "2_2") (pintype "passive"))
      (node (ref "C18") (pin "1") (pinfunction "1_1") (pintype "passive"))
      (node (ref "C19") (pin "1") (pinfunction "1_1") (pintype "passive"))
      (node (ref "C2") (pin "2") (pinfunction "2_2") (pintype "passive"))
      (node (ref "C20") (pin "1") (pinfunction "1_1") (pintype "passive"))
      (node (ref "C21") (pin "1") (pinfunction "1_1") (pintype "passive"))
      (node (ref "C22") (pin "2") (pinfunction "2_2") (pintype "passive"))
      (node (ref "C23") (pin "2") (pinfunction "2_2") (pintype "passive"))
      (node (ref "C24") (pin "2") (pinfunction "2_2") (pintype "passive"))
      (node (ref "C25") (pin "2") (pinfunction "2_2") (pintype "passive"))
      (node (ref "C26") (pin "1") (pinfunction "1_1") (pintype "passive"))
      (node (ref "C27") (pin "1") (pinfunction "1_1") (pintype "passive"))
      (node (ref "C28") (pin "2") (pinfunction "2_2") (pintype "passive"))
      (node (ref "C29") (pin "2") (pinfunction "2_2") (pintype "passive"))
      (node (ref "C3") (pin "1") (pinfunction "1_1") (pintype "passive"))
      (node (ref "C4") (pin "1") (pinfunction "1_1") (pintype "passive"))
      (node (ref "C5") (pin "1") (pinfunction "1_1") (pintype "passive"))
      (node (ref "C6") (pin "1") (pinfunction "1_1") (pintype "passive"))
      (node (ref "C7") (pin "1") (pinfunction "1_1") (pintype "passive"))
      (node (ref "C8") (pin "1") (pinfunction "1_1") (pintype "passive"))
      (node (ref "C9") (pin "2") (pinfunction "2_2") (pintype "passive"))
      (node (ref "CON1") (pin "0") (pinfunction "SH_0") (pintype "passive"))
      (node (ref "CON1") (pin "A12B1") (pinfunction "GND(A12B1)_A12B1") (pintype "passive"))
      (node (ref "CON1") (pin "A1B12") (pinfunction "GND(A1B12)_A1B12") (pintype "passive"))
      (node (ref "CON2") (pin "0") (pinfunction "SH_0") (pintype "passive"))
      (node (ref "CON2") (pin "A12B1") (pinfunction "GND(A12B1)_A12B1") (pintype "passive"))
      (node (ref "CON2") (pin "A1B12") (pinfunction "GND(A1B12)_A1B12") (pintype "passive"))
      (node (ref "CON3") (pin "0") (pinfunction "SH_0") (pintype "passive"))
      (node (ref "CON3") (pin "A12B1") (pinfunction "GND(A12B1)_A12B1") (pintype "passive"))
      (node (ref "CON3") (pin "A1B12") (pinfunction "GND(A1B12)_A1B12") (pintype "passive"))
      (node (ref "D10") (pin "2") (pinfunction "K_2") (pintype "passive"))
      (node (ref "D3") (pin "2") (pinfunction "K_2") (pintype "passive"))
      (node (ref "D5") (pin "2") (pinfunction "K_2") (pintype "passive"))
      (node (ref "D9") (pin "2") (pinfunction "K_2") (pintype "passive"))
      (node (ref "P1") (pin "1") (pinfunction "1_1") (pintype "passive"))
      (node (ref "P2") (pin "4") (pinfunction "4_4") (pintype "passive"))
      (node (ref "P3") (pin "1") (pinfunction "1_1") (pintype "passive"))
      (node (ref "P3") (pin "2") (pinfunction "2_2") (pintype "passive"))
      (node (ref "P3") (pin "27") (pinfunction "27_27") (pintype "passive"))
      (node (ref "P3") (pin "28") (pinfunction "28_28") (pintype "passive"))
      (node (ref "R15") (pin "1") (pinfunction "1_1") (pintype "passive"))
      (node (ref "R17") (pin "2") (pinfunction "2_2") (pintype "passive"))
      (node (ref "R18") (pin "2") (pinfunction "2_2") (pintype "passive"))
      (node (ref "R21") (pin "1") (pinfunction "1_1") (pintype "passive"))
      (node (ref "R22") (pin "1") (pinfunction "1_1") (pintype "passive"))
      (node (ref "R23") (pin "2") (pinfunction "2_2") (pintype "passive"))
      (node (ref "R8") (pin "1") (pinfunction "1_1") (pintype "passive"))
      (node (ref "U1") (pin "23") (pinfunction "VSS_1_23") (pintype "passive"))
      (node (ref "U1") (pin "35") (pinfunction "VSS_2_35") (pintype "passive"))
      (node (ref "U1") (pin "47") (pinfunction "VSS_3_47") (pintype "passive"))
      (node (ref "U1") (pin "49") (pinfunction "PAD_49") (pintype "passive"))
      (node (ref "U1") (pin "8") (pinfunction "VSSA_8") (pintype "passive"))
      (node (ref "U2") (pin "2") (pinfunction "GND_2") (pintype "passive"))
      (node (ref "U3") (pin "8") (pinfunction "VSS_8") (pintype "passive"))
      (node (ref "U4") (pin "2") (pinfunction "GND_2") (pintype "passive"))
      (node (ref "U5") (pin "10") (pinfunction "AGND_10") (pintype "power_in"))
      (node (ref "U5") (pin "12") (pinfunction "GND_12") (pintype "power_in"))
      (node (ref "U5") (pin "14") (pinfunction "RESERVED_14") (pintype "power_in"))
      (node (ref "U5") (pin "26") (pinfunction "GND_26") (pintype "power_in"))
      (node (ref "U5") (pin "28") (pinfunction "GND_28") (pintype "power_in"))
      (node (ref "U5") (pin "41") (pinfunction "GND_41") (pintype "power_in"))
      (node (ref "U5") (pin "53") (pinfunction "GND_53") (pintype "power_in"))
      (node (ref "U5") (pin "56") (pinfunction "GND_56") (pintype "power_in"))
      (node (ref "U5") (pin "57") (pinfunction "EP_57") (pintype "passive"))
      (node (ref "U5") (pin "6") (pinfunction "AGND_6") (pintype "power_in"))
      (node (ref "U6") (pin "1") (pinfunction "DIR_1") (pintype "passive"))
      (node (ref "U6") (pin "10") (pinfunction "GND_10") (pintype "passive"))
      (node (ref "U6") (pin "19") (pinfunction "OE_19") (pintype "passive"))
      (node (ref "U7") (pin "29") (pinfunction "HEAT_TAB_29") (pintype "passive"))
      (node (ref "U7") (pin "3") (pinfunction "GND_3") (pintype "passive"))
      (node (ref "U8") (pin "1") (pinfunction "A0_1") (pintype "input"))
      (node (ref "U8") (pin "2") (pinfunction "A1_2") (pintype "input"))
      (node (ref "U8") (pin "3") (pinfunction "A2_3") (pintype "input"))
      (node (ref "U8") (pin "4") (pinfunction "GND_4") (pintype "power_in"))
      (node (ref "U8") (pin "7") (pinfunction "WP_7") (pintype "input"))
    )
    (net (code "59") (name "L3.3V") (class "Default")
      (node (ref "C18") (pin "2") (pinfunction "2_2") (pintype "passive"))
      (node (ref "C19") (pin "2") (pinfunction "2_2") (pintype "passive"))
      (node (ref "C22") (pin "1") (pinfunction "1_1") (pintype "passive"))
      (node (ref "C23") (pin "1") (pinfunction "1_1") (pintype "passive"))
      (node (ref "C24") (pin "1") (pinfunction "1_1") (pintype "passive"))
      (node (ref "C25") (pin "1") (pinfunction "1_1") (pintype "passive"))
      (node (ref "P2") (pin "1") (pinfunction "1_1") (pintype "passive"))
      (node (ref "P3") (pin "20") (pinfunction "20_20") (pintype "passive"))
      (node (ref "P3") (pin "22") (pinfunction "22_22") (pintype "passive"))
      (node (ref "R28") (pin "5") (pinfunction "5_5") (pintype "passive"))
      (node (ref "R28") (pin "6") (pinfunction "6_6") (pintype "passive"))
      (node (ref "R28") (pin "7") (pinfunction "7_7") (pintype "passive"))
      (node (ref "R28") (pin "8") (pinfunction "8_8") (pintype "passive"))
      (node (ref "R29") (pin "5") (pinfunction "5_5") (pintype "passive"))
      (node (ref "R29") (pin "6") (pinfunction "6_6") (pintype "passive"))
      (node (ref "R29") (pin "7") (pinfunction "7_7") (pintype "passive"))
      (node (ref "R29") (pin "8") (pinfunction "8_8") (pintype "passive"))
      (node (ref "R30") (pin "2") (pinfunction "2_2") (pintype "passive"))
      (node (ref "R31") (pin "2") (pinfunction "2_2") (pintype "passive"))
      (node (ref "R32") (pin "1") (pinfunction "1_1") (pintype "passive"))
      (node (ref "R33") (pin "2") (pinfunction "2_2") (pintype "passive"))
      (node (ref "R36") (pin "1") (pinfunction "1_1") (pintype "passive"))
      (node (ref "U4") (pin "5") (pinfunction "VOUT_5") (pintype "passive"))
      (node (ref "U5") (pin "11") (pinfunction "VCC_11") (pintype "power_in"))
      (node (ref "U5") (pin "17") (pinfunction "VCC_17") (pintype "power_in"))
      (node (ref "U5") (pin "27") (pinfunction "VCC_27") (pintype "power_in"))
      (node (ref "U5") (pin "3") (pinfunction "AVCC_3") (pintype "power_in"))
      (node (ref "U5") (pin "32") (pinfunction "VCC_32") (pintype "power_in"))
      (node (ref "U5") (pin "43") (pinfunction "VCC_43") (pintype "power_in"))
      (node (ref "U5") (pin "55") (pinfunction "VCC_55") (pintype "power_in"))
      (node (ref "U5") (pin "7") (pinfunction "AVCC_7") (pintype "power_in"))
      (node (ref "U6") (pin "20") (pinfunction "VCC_20") (pintype "passive"))
      (node (ref "U8") (pin "8") (pinfunction "VCC_8") (pintype "power_in"))
    )
    (net (code "60") (name "LC_5V") (class "Default")
      (node (ref "C16") (pin "2") (pinfunction "2_2") (pintype "passive"))
      (node (ref "P3") (pin "24") (pinfunction "24_24") (pintype "passive"))
      (node (ref "P3") (pin "26") (pinfunction "26_26") (pintype "passive"))
      (node (ref "S3") (pin "1") (pinfunction "1_1") (pintype "passive"))
      (node (ref "U4") (pin "1") (pinfunction "VIN_1") (pintype "passive"))
      (node (ref "U4") (pin "3") (pinfunction "EN_3") (pintype "power_in"))
    )
    (net (code "61") (name "LK_5V") (class "Default")
      (node (ref "C8") (pin "2") (pinfunction "2_2") (pintype "passive"))
      (node (ref "S1") (pin "3") (pinfunction "3_3") (pintype "passive"))
      (node (ref "S2") (pin "1") (pinfunction "1_1") (pintype "passive"))
      (node (ref "U2") (pin "1") (pinfunction "VIN_1") (pintype "passive"))
      (node (ref "U2") (pin "3") (pinfunction "EN_3") (pintype "power_in"))
    )
    (net (code "62") (name "Net-(CON3-CC1(A5))") (class "Default")
      (node (ref "CON3") (pin "A5") (pinfunction "CC1(A5)_A5") (pintype "passive"))
      (node (ref "R17") (pin "1") (pinfunction "1_1") (pintype "passive"))
    )
    (net (code "63") (name "Net-(CON3-CC2(B5))") (class "Default")
      (node (ref "CON3") (pin "B5") (pinfunction "CC2(B5)_B5") (pintype "passive"))
      (node (ref "R21") (pin "2") (pinfunction "2_2") (pintype "passive"))
    )
    (net (code "64") (name "Net-(D1-A)") (class "Default")
      (node (ref "D1") (pin "1") (pinfunction "A_1") (pintype "passive"))
      (node (ref "R1") (pin "2") (pinfunction "2_2") (pintype "passive"))
    )
    (net (code "65") (name "Net-(D2-A)") (class "Default")
      (node (ref "D2") (pin "1") (pinfunction "A_1") (pintype "passive"))
      (node (ref "R3") (pin "2") (pinfunction "2_2") (pintype "passive"))
    )
    (net (code "66") (name "Net-(D3-A)") (class "Default")
      (node (ref "D3") (pin "1") (pinfunction "A_1") (pintype "passive"))
      (node (ref "R5") (pin "2") (pinfunction "2_2") (pintype "passive"))
    )
    (net (code "67") (name "Net-(D4-A)") (class "Default")
      (node (ref "D4") (pin "1") (pinfunction "A_1") (pintype "passive"))
      (node (ref "R7") (pin "2") (pinfunction "2_2") (pintype "passive"))
    )
    (net (code "68") (name "Net-(D5-A)") (class "Default")
      (node (ref "D5") (pin "1") (pinfunction "A_1") (pintype "passive"))
      (node (ref "R2") (pin "1") (pinfunction "1_1") (pintype "passive"))
    )
    (net (code "69") (name "Net-(D9-A)") (class "Default")
      (node (ref "D9") (pin "1") (pinfunction "A_1") (pintype "passive"))
      (node (ref "R13") (pin "1") (pinfunction "1_1") (pintype "passive"))
    )
    (net (code "70") (name "Net-(D10-A)") (class "Default")
      (node (ref "D10") (pin "1") (pinfunction "A_1") (pintype "passive"))
      (node (ref "R36") (pin "2") (pinfunction "2_2") (pintype "passive"))
    )
    (net (code "71") (name "Net-(U1A-BOOT0)") (class "Default")
      (node (ref "R8") (pin "2") (pinfunction "2_2") (pintype "passive"))
      (node (ref "U1") (pin "44") (pinfunction "BOOT0_44") (pintype "passive"))
    )
    (net (code "72") (name "Net-(U1A-OSC_IN)") (class "Default")
      (node (ref "C6") (pin "2") (pinfunction "2_2") (pintype "passive"))
      (node (ref "U1") (pin "5") (pinfunction "OSC_IN_5") (pintype "passive"))
      (node (ref "X1") (pin "1") (pinfunction "OSC1_1") (pintype "passive"))
    )
    (net (code "73") (name "Net-(U1A-OSC_OUT)") (class "Default")
      (node (ref "C7") (pin "2") (pinfunction "2_2") (pintype "passive"))
      (node (ref "U1") (pin "6") (pinfunction "OSC_OUT_6") (pintype "passive"))
      (node (ref "X1") (pin "2") (pinfunction "OSC2_2") (pintype "passive"))
    )
    (net (code "74") (name "Net-(U1B-PA0)") (class "Default")
      (node (ref "R14") (pin "1") (pinfunction "1_1") (pintype "passive"))
      (node (ref "R15") (pin "2") (pinfunction "2_2") (pintype "passive"))
      (node (ref "U1") (pin "10") (pinfunction "PA0_10") (pintype "passive"))
    )
    (net (code "75") (name "Net-(U1B-PB3)") (class "Default")
      (node (ref "R19") (pin "1") (pinfunction "1_1") (pintype "passive"))
      (node (ref "U1") (pin "39") (pinfunction "PB3_39") (pintype "passive"))
    )
    (net (code "76") (name "Net-(U1B-PB12)") (class "Default")
      (node (ref "R20") (pin "2") (pinfunction "2_2") (pintype "passive"))
      (node (ref "U1") (pin "25") (pinfunction "PB12_25") (pintype "passive"))
    )
    (net (code "77") (name "Net-(U1B-PC13)") (class "Default")
      (node (ref "R22") (pin "2") (pinfunction "2_2") (pintype "passive"))
      (node (ref "U1") (pin "2") (pinfunction "PC13_2") (pintype "passive"))
    )
    (net (code "78") (name "Net-(U1B-PC14)") (class "Default")
      (node (ref "R23") (pin "1") (pinfunction "1_1") (pintype "passive"))
      (node (ref "U1") (pin "3") (pinfunction "PC14_3") (pintype "passive"))
    )
    (net (code "79") (name "Net-(U2-BYP)") (class "Default")
      (node (ref "C12") (pin "2") (pinfunction "2_2") (pintype "passive"))
      (node (ref "U2") (pin "4") (pinfunction "BYP_4") (pintype "passive"))
    )
    (net (code "80") (name "Net-(U3-VDD18)") (class "Default")
      (node (ref "C15") (pin "1") (pinfunction "1_1") (pintype "passive"))
      (node (ref "U3") (pin "10") (pinfunction "VDD18_10") (pintype "passive"))
    )
    (net (code "81") (name "Net-(U3-VDD33)") (class "Default")
      (node (ref "C14") (pin "1") (pinfunction "1_1") (pintype "passive"))
      (node (ref "U3") (pin "9") (pinfunction "VDD33_9") (pintype "passive"))
    )
    (net (code "82") (name "Net-(U3-XIN)") (class "Default")
      (node (ref "C28") (pin "1") (pinfunction "1_1") (pintype "passive"))
      (node (ref "U3") (pin "12") (pinfunction "XIN_12") (pintype "passive"))
      (node (ref "X2") (pin "2") (pinfunction "OSC2_2") (pintype "passive"))
    )
    (net (code "83") (name "Net-(U3-XOUT)") (class "Default")
      (node (ref "C29") (pin "1") (pinfunction "1_1") (pintype "passive"))
      (node (ref "U3") (pin "11") (pinfunction "XOUT_11") (pintype "passive"))
      (node (ref "X2") (pin "1") (pinfunction "OSC1_1") (pintype "passive"))
    )
    (net (code "84") (name "Net-(U4-BYP)") (class "Default")
      (node (ref "C20") (pin "2") (pinfunction "2_2") (pintype "passive"))
      (node (ref "U4") (pin "4") (pinfunction "BYP_4") (pintype "passive"))
    )
    (net (code "85") (name "Net-(U5B-RESET#)") (class "Default")
      (node (ref "C27") (pin "2") (pinfunction "2_2") (pintype "passive"))
      (node (ref "R30") (pin "1") (pinfunction "1_1") (pintype "passive"))
      (node (ref "U5") (pin "42") (pinfunction "RESET#_42") (pintype "input"))
    )
    (net (code "86") (name "Net-(U5B-WAKEUP)") (class "Default")
      (node (ref "R33") (pin "1") (pinfunction "1_1") (pintype "passive"))
      (node (ref "U5") (pin "44") (pinfunction "WAKEUP_44") (pintype "input"))
    )
    (net (code "87") (name "Net-(U5B-XTALIN)") (class "Default")
      (node (ref "C9") (pin "1") (pinfunction "1_1") (pintype "passive"))
      (node (ref "U5") (pin "5") (pinfunction "XTALIN_5") (pintype "input"))
      (node (ref "X3") (pin "1") (pinfunction "OSC1_1") (pintype "passive"))
    )
    (net (code "88") (name "Net-(U5B-XTALOUT)") (class "Default")
      (node (ref "C17") (pin "1") (pinfunction "1_1") (pintype "passive"))
      (node (ref "U5") (pin "4") (pinfunction "XTALOUT_4") (pintype "passive"))
      (node (ref "X3") (pin "2") (pinfunction "OSC2_2") (pintype "passive"))
    )
    (net (code "89") (name "Net-(U6-B0)") (class "Default")
      (node (ref "R25") (pin "1") (pinfunction "1_1") (pintype "passive"))
      (node (ref "R28") (pin "4") (pinfunction "4_4") (pintype "passive"))
      (node (ref "U6") (pin "18") (pinfunction "B0_18") (pintype "passive"))
    )
    (net (code "90") (name "Net-(U6-B1)") (class "Default")
      (node (ref "R25") (pin "2") (pinfunction "2_2") (pintype "passive"))
      (node (ref "R28") (pin "3") (pinfunction "3_3") (pintype "passive"))
      (node (ref "U6") (pin "17") (pinfunction "B1_17") (pintype "passive"))
    )
    (net (code "91") (name "Net-(U6-B2)") (class "Default")
      (node (ref "R25") (pin "3") (pinfunction "3_3") (pintype "passive"))
      (node (ref "R28") (pin "2") (pinfunction "2_2") (pintype "passive"))
      (node (ref "U6") (pin "16") (pinfunction "B2_16") (pintype "passive"))
    )
    (net (code "92") (name "Net-(U6-B3)") (class "Default")
      (node (ref "R25") (pin "4") (pinfunction "4_4") (pintype "passive"))
      (node (ref "R28") (pin "1") (pinfunction "1_1") (pintype "passive"))
      (node (ref "U6") (pin "15") (pinfunction "B3_15") (pintype "passive"))
    )
    (net (code "93") (name "Net-(U6-B4)") (class "Default")
      (node (ref "R27") (pin "1") (pinfunction "1_1") (pintype "passive"))
      (node (ref "R29") (pin "4") (pinfunction "4_4") (pintype "passive"))
      (node (ref "U6") (pin "14") (pinfunction "B4_14") (pintype "passive"))
    )
    (net (code "94") (name "Net-(U6-B5)") (class "Default")
      (node (ref "R27") (pin "2") (pinfunction "2_2") (pintype "passive"))
      (node (ref "R29") (pin "3") (pinfunction "3_3") (pintype "passive"))
      (node (ref "U6") (pin "13") (pinfunction "B5_13") (pintype "passive"))
    )
    (net (code "95") (name "Net-(U6-B6)") (class "Default")
      (node (ref "R27") (pin "3") (pinfunction "3_3") (pintype "passive"))
      (node (ref "R29") (pin "2") (pinfunction "2_2") (pintype "passive"))
      (node (ref "U6") (pin "12") (pinfunction "B6_12") (pintype "passive"))
    )
    (net (code "96") (name "Net-(U6-B7)") (class "Default")
      (node (ref "R27") (pin "4") (pinfunction "4_4") (pintype "passive"))
      (node (ref "R29") (pin "1") (pinfunction "1_1") (pintype "passive"))
      (node (ref "U6") (pin "11") (pinfunction "B7_11") (pintype "passive"))
    )
    (net (code "97") (name "Net-(U7-*RST)") (class "Default")
      (node (ref "R26") (pin "1") (pinfunction "1_1") (pintype "passive"))
      (node (ref "U7") (pin "9") (pinfunction "*RST_9") (pintype "passive"))
    )
    (net (code "98") (name "USB_5V") (class "Default")
      (node (ref "C13") (pin "2") (pinfunction "2_2") (pintype "passive"))
      (node (ref "C26") (pin "2") (pinfunction "2_2") (pintype "passive"))
      (node (ref "CON2") (pin "A4B9") (pinfunction "VBUS(A4B9)_A4B9") (pintype "passive"))
      (node (ref "CON2") (pin "A9B4") (pinfunction "VBUS(A9B4)_A9B4") (pintype "passive"))
      (node (ref "CON3") (pin "A4B9") (pinfunction "VBUS(A4B9)_A4B9") (pintype "passive"))
      (node (ref "CON3") (pin "A9B4") (pinfunction "VBUS(A9B4)_A9B4") (pintype "passive"))
      (node (ref "P3") (pin "17") (pinfunction "17_17") (pintype "passive"))
      (node (ref "S2") (pin "2") (pinfunction "2_2") (pintype "passive"))
      (node (ref "S3") (pin "2") (pinfunction "2_2") (pintype "passive"))
      (node (ref "U3") (pin "7") (pinfunction "VDD5_7") (pintype "passive"))
      (node (ref "U7") (pin "7") (pinfunction "REGIN_7") (pintype "passive"))
      (node (ref "U7") (pin "8") (pinfunction "VBUS_8") (pintype "passive"))
    )
    (net (code "99") (name "VCC") (class "Default")
      (node (ref "CON1") (pin "A4B9") (pinfunction "VBUS(A4B9)_A4B9") (pintype "passive"))
      (node (ref "CON1") (pin "A9B4") (pinfunction "VBUS(A9B4)_A9B4") (pintype "passive"))
      (node (ref "P3") (pin "15") (pinfunction "15_15") (pintype "passive"))
      (node (ref "S1") (pin "2") (pinfunction "2_2") (pintype "passive"))
    )
    (net (code "100") (name "unconnected-(CON1-CC1(A5)-PadA5)") (class "Default")
      (node (ref "CON1") (pin "A5") (pinfunction "CC1(A5)_A5") (pintype "passive+no_connect"))
    )
    (net (code "101") (name "unconnected-(CON1-CC2(B5)-PadB5)") (class "Default")
      (node (ref "CON1") (pin "B5") (pinfunction "CC2(B5)_B5") (pintype "passive+no_connect"))
    )
    (net (code "102") (name "unconnected-(CON1-SBU1(A8)-PadA8)") (class "Default")
      (node (ref "CON1") (pin "A8") (pinfunction "SBU1(A8)_A8") (pintype "passive+no_connect"))
    )
    (net (code "103") (name "unconnected-(CON1-SBU2(B8)-PadB8)") (class "Default")
      (node (ref "CON1") (pin "B8") (pinfunction "SBU2(B8)_B8") (pintype "passive+no_connect"))
    )
    (net (code "104") (name "unconnected-(CON2-CC1(A5)-PadA5)") (class "Default")
      (node (ref "CON2") (pin "A5") (pinfunction "CC1(A5)_A5") (pintype "passive+no_connect"))
    )
    (net (code "105") (name "unconnected-(CON2-CC2(B5)-PadB5)") (class "Default")
      (node (ref "CON2") (pin "B5") (pinfunction "CC2(B5)_B5") (pintype "passive+no_connect"))
    )
    (net (code "106") (name "unconnected-(CON2-SBU1(A8)-PadA8)") (class "Default")
      (node (ref "CON2") (pin "A8") (pinfunction "SBU1(A8)_A8") (pintype "passive+no_connect"))
    )
    (net (code "107") (name "unconnected-(CON2-SBU2(B8)-PadB8)") (class "Default")
      (node (ref "CON2") (pin "B8") (pinfunction "SBU2(B8)_B8") (pintype "passive+no_connect"))
    )
    (net (code "108") (name "unconnected-(CON3-SBU1(A8)-PadA8)") (class "Default")
      (node (ref "CON3") (pin "A8") (pinfunction "SBU1(A8)_A8") (pintype "passive+no_connect"))
    )
    (net (code "109") (name "unconnected-(CON3-SBU2(B8)-PadB8)") (class "Default")
      (node (ref "CON3") (pin "B8") (pinfunction "SBU2(B8)_B8") (pintype "passive+no_connect"))
    )
    (net (code "110") (name "unconnected-(S2-Pad3)") (class "Default")
      (node (ref "S2") (pin "3") (pinfunction "3_3") (pintype "passive"))
    )
    (net (code "111") (name "unconnected-(S3-Pad3)") (class "Default")
      (node (ref "S3") (pin "3") (pinfunction "3_3") (pintype "passive"))
    )
    (net (code "112") (name "unconnected-(U1B-PA1-Pad11)") (class "Default")
      (node (ref "U1") (pin "11") (pinfunction "PA1_11") (pintype "passive+no_connect"))
    )
    (net (code "113") (name "unconnected-(U1B-PA4-Pad14)") (class "Default")
      (node (ref "U1") (pin "14") (pinfunction "PA4_14") (pintype "passive+no_connect"))
    )
    (net (code "114") (name "unconnected-(U1B-PA6-Pad16)") (class "Default")
      (node (ref "U1") (pin "16") (pinfunction "PA6_16") (pintype "passive+no_connect"))
    )
    (net (code "115") (name "unconnected-(U1B-PA7-Pad17)") (class "Default")
      (node (ref "U1") (pin "17") (pinfunction "PA7_17") (pintype "passive+no_connect"))
    )
    (net (code "116") (name "unconnected-(U1B-PA8-Pad29)") (class "Default")
      (node (ref "U1") (pin "29") (pinfunction "PA8_29") (pintype "passive+no_connect"))
    )
    (net (code "117") (name "unconnected-(U1B-PB1-Pad19)") (class "Default")
      (node (ref "U1") (pin "19") (pinfunction "PB1_19") (pintype "passive"))
    )
    (net (code "118") (name "unconnected-(U1B-PB5-Pad41)") (class "Default")
      (node (ref "U1") (pin "41") (pinfunction "PB5_41") (pintype "passive+no_connect"))
    )
    (net (code "119") (name "unconnected-(U1B-PB7-Pad43)") (class "Default")
      (node (ref "U1") (pin "43") (pinfunction "PB7_43") (pintype "passive+no_connect"))
    )
    (net (code "120") (name "unconnected-(U1B-PB8-Pad45)") (class "Default")
      (node (ref "U1") (pin "45") (pinfunction "PB8_45") (pintype "passive+no_connect"))
    )
    (net (code "121") (name "unconnected-(U1B-PB9-Pad46)") (class "Default")
      (node (ref "U1") (pin "46") (pinfunction "PB9_46") (pintype "passive+no_connect"))
    )
    (net (code "122") (name "unconnected-(U1B-PB10-Pad21)") (class "Default")
      (node (ref "U1") (pin "21") (pinfunction "PB10_21") (pintype "passive+no_connect"))
    )
    (net (code "123") (name "unconnected-(U1B-PB11-Pad22)") (class "Default")
      (node (ref "U1") (pin "22") (pinfunction "PB11_22") (pintype "passive+no_connect"))
    )
    (net (code "124") (name "unconnected-(U1B-PB15-Pad28)") (class "Default")
      (node (ref "U1") (pin "28") (pinfunction "PB15_28") (pintype "passive+no_connect"))
    )
    (net (code "125") (name "unconnected-(U1B-PC15-Pad4)") (class "Default")
      (node (ref "U1") (pin "4") (pinfunction "PC15_4") (pintype "passive+no_connect"))
    )
    (net (code "126") (name "unconnected-(U5A-PA2{slash}SLOE-Pad35)") (class "Default")
      (node (ref "U5") (pin "35") (pinfunction "PA2/SLOE_35") (pintype "bidirectional+no_connect"))
    )
    (net (code "127") (name "unconnected-(U5A-PA3{slash}WU2-Pad36)") (class "Default")
      (node (ref "U5") (pin "36") (pinfunction "PA3/WU2_36") (pintype "bidirectional+no_connect"))
    )
    (net (code "128") (name "unconnected-(U5A-PA4{slash}FIFOADR0-Pad37)") (class "Default")
      (node (ref "U5") (pin "37") (pinfunction "PA4/FIFOADR0_37") (pintype "bidirectional+no_connect"))
    )
    (net (code "129") (name "unconnected-(U5A-PA5{slash}FIFOADR1-Pad38)") (class "Default")
      (node (ref "U5") (pin "38") (pinfunction "PA5/FIFOADR1_38") (pintype "bidirectional+no_connect"))
    )
    (net (code "130") (name "unconnected-(U5A-PA6{slash}PKTEND-Pad39)") (class "Default")
      (node (ref "U5") (pin "39") (pinfunction "PA6/PKTEND_39") (pintype "bidirectional+no_connect"))
    )
    (net (code "131") (name "unconnected-(U5A-PA7{slash}FLAGD{slash}SLCS#-Pad40)") (class "Default")
      (node (ref "U5") (pin "40") (pinfunction "PA7/FLAGD/SLCS#_40") (pintype "bidirectional+no_connect"))
    )
    (net (code "132") (name "unconnected-(U5A-PD0{slash}FD8-Pad45)") (class "Default")
      (node (ref "U5") (pin "45") (pinfunction "PD0/FD8_45") (pintype "bidirectional+no_connect"))
    )
    (net (code "133") (name "unconnected-(U5A-PD1{slash}FD9-Pad46)") (class "Default")
      (node (ref "U5") (pin "46") (pinfunction "PD1/FD9_46") (pintype "bidirectional+no_connect"))
    )
    (net (code "134") (name "unconnected-(U5A-PD2{slash}FD10-Pad47)") (class "Default")
      (node (ref "U5") (pin "47") (pinfunction "PD2/FD10_47") (pintype "bidirectional+no_connect"))
    )
    (net (code "135") (name "unconnected-(U5A-PD3{slash}FD11-Pad48)") (class "Default")
      (node (ref "U5") (pin "48") (pinfunction "PD3/FD11_48") (pintype "bidirectional+no_connect"))
    )
    (net (code "136") (name "unconnected-(U5A-PD4{slash}FD12-Pad49)") (class "Default")
      (node (ref "U5") (pin "49") (pinfunction "PD4/FD12_49") (pintype "bidirectional+no_connect"))
    )
    (net (code "137") (name "unconnected-(U5A-PD5{slash}FD13-Pad50)") (class "Default")
      (node (ref "U5") (pin "50") (pinfunction "PD5/FD13_50") (pintype "bidirectional+no_connect"))
    )
    (net (code "138") (name "unconnected-(U5A-PD6{slash}FD14-Pad51)") (class "Default")
      (node (ref "U5") (pin "51") (pinfunction "PD6/FD14_51") (pintype "bidirectional+no_connect"))
    )
    (net (code "139") (name "unconnected-(U5A-PD7{slash}FD15-Pad52)") (class "Default")
      (node (ref "U5") (pin "52") (pinfunction "PD7/FD15_52") (pintype "bidirectional+no_connect"))
    )
    (net (code "140") (name "unconnected-(U5B-CLKOUT-Pad54)") (class "Default")
      (node (ref "U5") (pin "54") (pinfunction "CLKOUT_54") (pintype "tri_state+no_connect"))
    )
    (net (code "141") (name "unconnected-(U5B-CTL0{slash}FLAGA-Pad29)") (class "Default")
      (node (ref "U5") (pin "29") (pinfunction "CTL0/FLAGA_29") (pintype "tri_state+no_connect"))
    )
    (net (code "142") (name "unconnected-(U5B-CTL1{slash}FLAGB-Pad30)") (class "Default")
      (node (ref "U5") (pin "30") (pinfunction "CTL1/FLAGB_30") (pintype "tri_state+no_connect"))
    )
    (net (code "143") (name "unconnected-(U5B-CTL2{slash}FLAGC-Pad31)") (class "Default")
      (node (ref "U5") (pin "31") (pinfunction "CTL2/FLAGC_31") (pintype "tri_state+no_connect"))
    )
    (net (code "144") (name "unconnected-(U5B-IFCLK-Pad13)") (class "Default")
      (node (ref "U5") (pin "13") (pinfunction "IFCLK_13") (pintype "bidirectional+no_connect"))
    )
    (net (code "145") (name "unconnected-(U5B-RDY0{slash}SLRD-Pad1)") (class "Default")
      (node (ref "U5") (pin "1") (pinfunction "RDY0/SLRD_1") (pintype "input+no_connect"))
    )
    (net (code "146") (name "unconnected-(U5B-RDY1{slash}SLWR-Pad2)") (class "Default")
      (node (ref "U5") (pin "2") (pinfunction "RDY1/SLWR_2") (pintype "input+no_connect"))
    )
    (net (code "147") (name "unconnected-(U7-*SUSPEND-Pad11)") (class "Default")
      (node (ref "U7") (pin "11") (pinfunction "*SUSPEND_11") (pintype "passive+no_connect"))
    )
    (net (code "148") (name "unconnected-(U7-CTS-Pad23)") (class "Default")
      (node (ref "U7") (pin "23") (pinfunction "CTS_23") (pintype "passive+no_connect"))
    )
    (net (code "149") (name "unconnected-(U7-DCD-Pad1)") (class "Default")
      (node (ref "U7") (pin "1") (pinfunction "DCD_1") (pintype "passive+no_connect"))
    )
    (net (code "150") (name "unconnected-(U7-DSR-Pad27)") (class "Default")
      (node (ref "U7") (pin "27") (pinfunction "DSR_27") (pintype "passive+no_connect"))
    )
    (net (code "151") (name "unconnected-(U7-NC-Pad10)") (class "Default")
      (node (ref "U7") (pin "10") (pinfunction "NC_10") (pintype "passive+no_connect"))
    )
    (net (code "152") (name "unconnected-(U7-NC-Pad13)") (class "Default")
      (node (ref "U7") (pin "13") (pinfunction "NC_13") (pintype "passive+no_connect"))
    )
    (net (code "153") (name "unconnected-(U7-NC-Pad14)") (class "Default")
      (node (ref "U7") (pin "14") (pinfunction "NC_14") (pintype "passive+no_connect"))
    )
    (net (code "154") (name "unconnected-(U7-NC-Pad15)") (class "Default")
      (node (ref "U7") (pin "15") (pinfunction "NC_15") (pintype "passive+no_connect"))
    )
    (net (code "155") (name "unconnected-(U7-NC-Pad16)") (class "Default")
      (node (ref "U7") (pin "16") (pinfunction "NC_16") (pintype "passive+no_connect"))
    )
    (net (code "156") (name "unconnected-(U7-NC-Pad17)") (class "Default")
      (node (ref "U7") (pin "17") (pinfunction "NC_17") (pintype "passive+no_connect"))
    )
    (net (code "157") (name "unconnected-(U7-NC-Pad18)") (class "Default")
      (node (ref "U7") (pin "18") (pinfunction "NC_18") (pintype "passive+no_connect"))
    )
    (net (code "158") (name "unconnected-(U7-NC-Pad19)") (class "Default")
      (node (ref "U7") (pin "19") (pinfunction "NC_19") (pintype "passive+no_connect"))
    )
    (net (code "159") (name "unconnected-(U7-NC-Pad20)") (class "Default")
      (node (ref "U7") (pin "20") (pinfunction "NC_20") (pintype "passive+no_connect"))
    )
    (net (code "160") (name "unconnected-(U7-NC-Pad21)") (class "Default")
      (node (ref "U7") (pin "21") (pinfunction "NC_21") (pintype "passive+no_connect"))
    )
    (net (code "161") (name "unconnected-(U7-NC-Pad22)") (class "Default")
      (node (ref "U7") (pin "22") (pinfunction "NC_22") (pintype "passive+no_connect"))
    )
    (net (code "162") (name "unconnected-(U7-RI-Pad2)") (class "Default")
      (node (ref "U7") (pin "2") (pinfunction "RI_2") (pintype "passive+no_connect"))
    )
    (net (code "163") (name "unconnected-(U7-SUSPEND-Pad12)") (class "Default")
      (node (ref "U7") (pin "12") (pinfunction "SUSPEND_12") (pintype "passive+no_connect"))
    )
  )
)
